# BoardSchematic.net
KiCad netlist of a schematic drawn in EAGLE
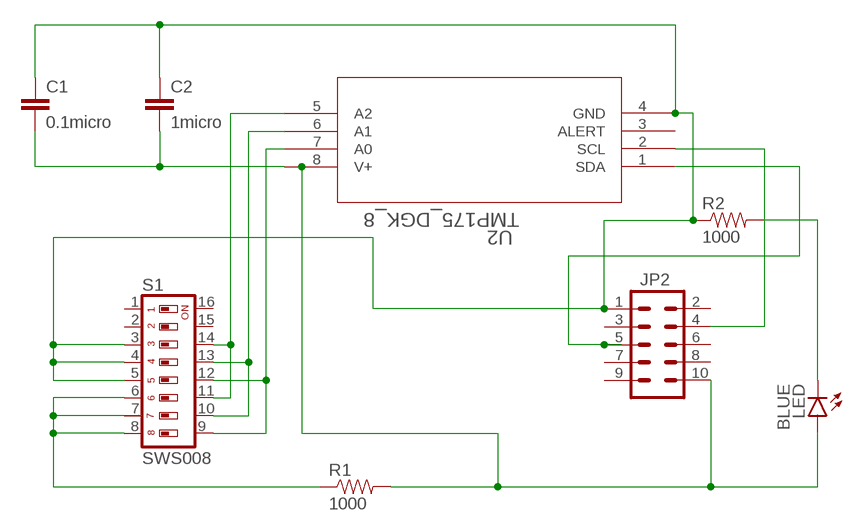
[diagram p0: schematic, sheet 1]

(export (version "E")
  (design (tool "Eeschema 10.0.6"))
  (components
    (comp (ref "C1")
      (value "0.1micro")
      (footprint "eagle-import:0805")
      (libsource (lib "eagle-import") (part "22UF-6.3V-20%(0805)"))
    )
    (comp (ref "C2")
      (value "1micro")
      (footprint "eagle-import:1210")
      (libsource (lib "eagle-import") (part "22UF-16V-20%-(1210)"))
    )
    (comp (ref "JP2")
      (value "M05X2PTH")
      (footprint "eagle-import:AVR_ICSP")
      (libsource (lib "eagle-import") (part "M05X2PTH"))
    )
    (comp (ref "LED")
      (value "BLUE")
      (footprint "eagle-import:LED-1206")
      (libsource (lib "eagle-import") (part "LED-BLUE1206"))
    )
    (comp (ref "R1")
      (value "1000")
      (footprint "eagle-import:0805")
      (libsource (lib "eagle-import") (part "RESISTOR0805-RES"))
    )
    (comp (ref "R2")
      (value "1000")
      (footprint "eagle-import:0805")
      (libsource (lib "eagle-import") (part "RESISTOR0805-RES"))
    )
    (comp (ref "S1")
      (value "SWS008")
      (footprint "eagle-import:SMS-008")
      (libsource (lib "eagle-import") (part "SWS008"))
    )
    (comp (ref "U2")
      (value "TMP175_DGK_8")
      (footprint "eagle-import:DGK8")
      (fields
        (field (name "GENERIC_PART_NUMBER") "TMP175")
        (field (name "MANUFACTURER") "Texas Instruments")
        (field (name "MANUFACTURER_PART_NUMBER") "tmp175_dgk_8")
      )
      (libsource (lib "eagle-import") (part "TMP175_DGK_8"))
    )
  )
  (nets
    (net (code "1") (name "Net-(JP2-Pad10)") (class "Default")
      (node (ref "JP2") (pin "10") (pinfunction "10_10") (pintype "passive"))
      (node (ref "LED") (pin "A") (pinfunction "A_A") (pintype "passive"))
      (node (ref "R1") (pin "2") (pinfunction "2_2") (pintype "passive"))
    )
    (net (code "2") (name "Net-(LED-PadC)") (class "Default")
      (node (ref "LED") (pin "C") (pinfunction "C_C") (pintype "passive"))
      (node (ref "R2") (pin "2") (pinfunction "2_2") (pintype "passive"))
    )
    (net (code "3") (name "Net-(R1-Pad1)") (class "Default")
      (node (ref "R1") (pin "1") (pinfunction "1_1") (pintype "passive"))
      (node (ref "S1") (pin "6") (pinfunction "6_6") (pintype "passive"))
      (node (ref "S1") (pin "8") (pinfunction "8_8") (pintype "passive"))
    )
    (net (code "4") (name "Net-(U2-A0)") (class "Default")
      (node (ref "S1") (pin "12") (pinfunction "12_12") (pintype "passive"))
      (node (ref "S1") (pin "9") (pinfunction "9_9") (pintype "passive"))
      (node (ref "U2") (pin "7") (pinfunction "A0_7") (pintype "bidirectional"))
    )
    (net (code "5") (name "Net-(U2-A1)") (class "Default")
      (node (ref "S1") (pin "10") (pinfunction "10_10") (pintype "passive"))
      (node (ref "S1") (pin "13") (pinfunction "13_13") (pintype "passive"))
      (node (ref "U2") (pin "6") (pinfunction "A1_6") (pintype "bidirectional"))
    )
    (net (code "6") (name "Net-(U2-A2)") (class "Default")
      (node (ref "S1") (pin "11") (pinfunction "11_11") (pintype "passive"))
      (node (ref "S1") (pin "14") (pinfunction "14_14") (pintype "passive"))
      (node (ref "U2") (pin "5") (pinfunction "A2_5") (pintype "bidirectional"))
    )
    (net (code "7") (name "Net-(U2-GND)") (class "Default")
      (node (ref "C1") (pin "1") (pinfunction "1_1") (pintype "passive"))
      (node (ref "C2") (pin "1") (pinfunction "1_1") (pintype "passive"))
      (node (ref "JP2") (pin "1") (pinfunction "1_1") (pintype "passive"))
      (node (ref "R2") (pin "1") (pinfunction "1_1") (pintype "passive"))
      (node (ref "S1") (pin "3") (pinfunction "3_3") (pintype "passive"))
      (node (ref "S1") (pin "4") (pinfunction "4_4") (pintype "passive"))
      (node (ref "S1") (pin "5") (pinfunction "5_5") (pintype "passive"))
      (node (ref "U2") (pin "4") (pinfunction "GND_4") (pintype "power_in"))
    )
    (net (code "8") (name "Net-(U2-SCL)") (class "Default")
      (node (ref "JP2") (pin "4") (pinfunction "4_4") (pintype "passive"))
      (node (ref "U2") (pin "2") (pinfunction "SCL_2") (pintype "bidirectional"))
    )
    (net (code "9") (name "Net-(U2-SDA)") (class "Default")
      (node (ref "JP2") (pin "5") (pinfunction "5_5") (pintype "passive"))
      (node (ref "U2") (pin "1") (pinfunction "SDA_1") (pintype "bidirectional"))
    )
    (net (code "10") (name "Net-(U2-V+)") (class "Default")
      (node (ref "C1") (pin "2") (pinfunction "2_2") (pintype "passive"))
      (node (ref "C2") (pin "2") (pinfunction "2_2") (pintype "passive"))
      (node (ref "U2") (pin "8") (pinfunction "V+_8") (pintype "power_in"))
    )
    (net (code "11") (name "unconnected-(JP2-Pad2)") (class "Default")
      (node (ref "JP2") (pin "2") (pinfunction "2_2") (pintype "passive"))
    )
    (net (code "12") (name "unconnected-(JP2-Pad3)") (class "Default")
      (node (ref "JP2") (pin "3") (pinfunction "3_3") (pintype "passive"))
    )
    (net (code "13") (name "unconnected-(JP2-Pad6)") (class "Default")
      (node (ref "JP2") (pin "6") (pinfunction "6_6") (pintype "passive"))
    )
    (net (code "14") (name "unconnected-(JP2-Pad7)") (class "Default")
      (node (ref "JP2") (pin "7") (pinfunction "7_7") (pintype "passive"))
    )
    (net (code "15") (name "unconnected-(JP2-Pad8)") (class "Default")
      (node (ref "JP2") (pin "8") (pinfunction "8_8") (pintype "passive"))
    )
    (net (code "16") (name "unconnected-(JP2-Pad9)") (class "Default")
      (node (ref "JP2") (pin "9") (pinfunction "9_9") (pintype "passive"))
    )
    (net (code "17") (name "unconnected-(S1-Pad1)") (class "Default")
      (node (ref "S1") (pin "1") (pinfunction "1_1") (pintype "passive"))
    )
    (net (code "18") (name "unconnected-(S1-Pad2)") (class "Default")
      (node (ref "S1") (pin "2") (pinfunction "2_2") (pintype "passive"))
    )
    (net (code "19") (name "unconnected-(S1-Pad7)") (class "Default")
      (node (ref "S1") (pin "7") (pinfunction "7_7") (pintype "passive"))
    )
    (net (code "20") (name "unconnected-(S1-Pad15)") (class "Default")
      (node (ref "S1") (pin "15") (pinfunction "15_15") (pintype "passive"))
    )
    (net (code "21") (name "unconnected-(S1-Pad16)") (class "Default")
      (node (ref "S1") (pin "16") (pinfunction "16_16") (pintype "passive"))
    )
    (net (code "22") (name "unconnected-(U2-ALERT-Pad3)") (class "Default")
      (node (ref "U2") (pin "3") (pinfunction "ALERT_3") (pintype "bidirectional"))
    )
  )
)
